# ANET3D_LCD2004_board.net
KiCad netlist of a schematic drawn in EAGLE
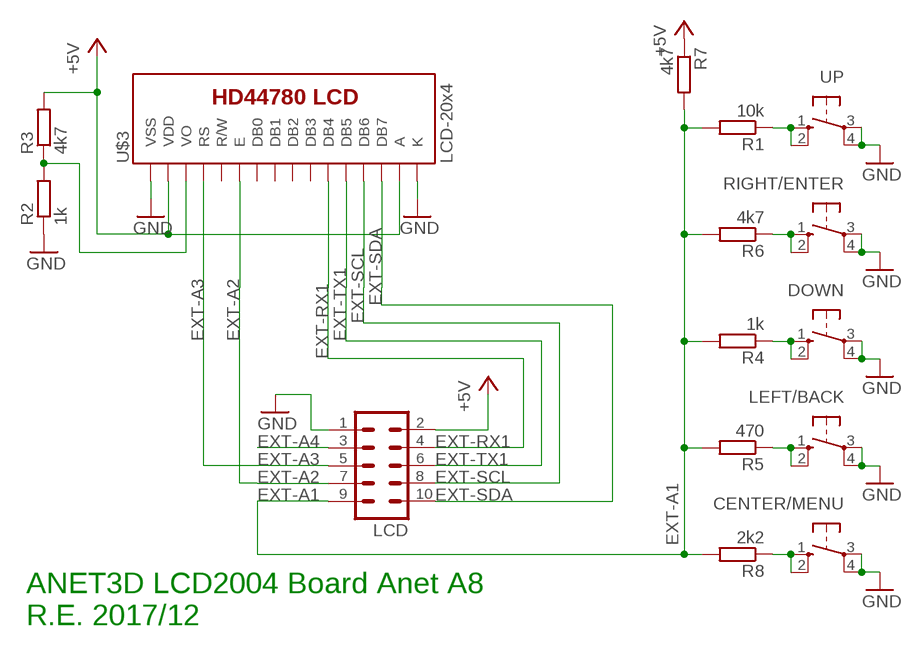
[diagram p0: schematic, sheet 1]

(export (version "E")
  (design (tool "Eeschema 10.0.6"))
  (components
    (comp (ref "CENTER/MENU")
      (value "40-XX")
      (footprint "eagle-import:B3F-40XX")
      (fields (field (name "MF") "OMRON COMPONENTS USA") (field (name "MPN") "B3F-4000"))
      (libsource (lib "eagle-import") (part "40-XX"))
    )
    (comp (ref "DOWN")
      (value "40-XX")
      (footprint "eagle-import:B3F-40XX")
      (fields (field (name "MF") "OMRON COMPONENTS USA") (field (name "MPN") "B3F-4000"))
      (libsource (lib "eagle-import") (part "40-XX"))
    )
    (comp (ref "LCD1")
      (value "LCD")
      (footprint "eagle-import:ML10")
      (libsource (lib "eagle-import") (part "ML10"))
    )
    (comp (ref "LEFT/BACK")
      (value "40-XX")
      (footprint "eagle-import:B3F-40XX")
      (fields (field (name "MF") "OMRON COMPONENTS USA") (field (name "MPN") "B3F-4000"))
      (libsource (lib "eagle-import") (part "40-XX"))
    )
    (comp (ref "R1")
      (value "10k")
      (footprint "eagle-import:R0805")
      (libsource (lib "eagle-import") (part "R-EU_R0805"))
    )
    (comp (ref "R2")
      (value "1k")
      (footprint "eagle-import:R0805")
      (libsource (lib "eagle-import") (part "R-EU_R0805"))
    )
    (comp (ref "R3")
      (value "4k7")
      (footprint "eagle-import:R0805")
      (libsource (lib "eagle-import") (part "R-EU_R0805"))
    )
    (comp (ref "R4")
      (value "1k")
      (footprint "eagle-import:R0805")
      (libsource (lib "eagle-import") (part "R-EU_R0805"))
    )
    (comp (ref "R5")
      (value "470")
      (footprint "eagle-import:R0805")
      (libsource (lib "eagle-import") (part "R-EU_R0805"))
    )
    (comp (ref "R6")
      (value "4k7")
      (footprint "eagle-import:R0805")
      (libsource (lib "eagle-import") (part "R-EU_R0805"))
    )
    (comp (ref "R7")
      (value "4k7")
      (footprint "eagle-import:R0805")
      (libsource (lib "eagle-import") (part "R-EU_R0805"))
    )
    (comp (ref "R8")
      (value "2k2")
      (footprint "eagle-import:R0805")
      (libsource (lib "eagle-import") (part "R-EU_R0805"))
    )
    (comp (ref "RIGHT/ENTER")
      (value "40-XX")
      (footprint "eagle-import:B3F-40XX")
      (fields (field (name "MF") "OMRON COMPONENTS USA") (field (name "MPN") "B3F-4000"))
      (libsource (lib "eagle-import") (part "40-XX"))
    )
    (comp (ref "U$3")
      (value "LCD-20x4")
      (footprint "eagle-import:LCD-20X4-4HOLES")
      (libsource (lib "eagle-import") (part "LCD-HD4478020X4-4HOLES4-HOLES"))
    )
    (comp (ref "UP")
      (value "40-XX")
      (footprint "eagle-import:B3F-40XX")
      (fields (field (name "MF") "OMRON COMPONENTS USA") (field (name "MPN") "B3F-4000"))
      (libsource (lib "eagle-import") (part "40-XX"))
    )
  )
  (nets
    (net (code "1") (name "+5V") (class "Default")
      (node (ref "LCD1") (pin "2") (pinfunction "2_2") (pintype "passive"))
      (node (ref "R3") (pin "2") (pinfunction "2_2") (pintype "passive"))
      (node (ref "R7") (pin "1") (pinfunction "1_1") (pintype "passive"))
      (node (ref "U$3") (pin "P$15") (pinfunction "A_P$15") (pintype "power_in"))
      (node (ref "U$3") (pin "P$2") (pinfunction "VDD_P$2") (pintype "power_in"))
    )
    (net (code "2") (name "/EXT-A1") (class "Default")
      (node (ref "LCD1") (pin "9") (pinfunction "9_9") (pintype "passive"))
      (node (ref "R1") (pin "2") (pinfunction "2_2") (pintype "passive"))
      (node (ref "R4") (pin "2") (pinfunction "2_2") (pintype "passive"))
      (node (ref "R5") (pin "2") (pinfunction "2_2") (pintype "passive"))
      (node (ref "R6") (pin "2") (pinfunction "2_2") (pintype "passive"))
      (node (ref "R7") (pin "2") (pinfunction "2_2") (pintype "passive"))
      (node (ref "R8") (pin "2") (pinfunction "2_2") (pintype "passive"))
    )
    (net (code "3") (name "/EXT-A2") (class "Default")
      (node (ref "LCD1") (pin "7") (pinfunction "7_7") (pintype "passive"))
      (node (ref "U$3") (pin "P$6") (pinfunction "E_P$6") (pintype "input"))
    )
    (net (code "4") (name "/EXT-A3") (class "Default")
      (node (ref "LCD1") (pin "5") (pinfunction "5_5") (pintype "passive"))
      (node (ref "U$3") (pin "P$4") (pinfunction "RS_P$4") (pintype "input"))
    )
    (net (code "5") (name "/EXT-A4") (class "Default")
      (node (ref "LCD1") (pin "3") (pinfunction "3_3") (pintype "passive"))
    )
    (net (code "6") (name "/EXT-RX1") (class "Default")
      (node (ref "LCD1") (pin "4") (pinfunction "4_4") (pintype "passive"))
      (node (ref "U$3") (pin "P$11") (pinfunction "DB4_P$11") (pintype "bidirectional"))
    )
    (net (code "7") (name "/EXT-SCL") (class "Default")
      (node (ref "LCD1") (pin "8") (pinfunction "8_8") (pintype "passive"))
      (node (ref "U$3") (pin "P$13") (pinfunction "DB6_P$13") (pintype "bidirectional"))
    )
    (net (code "8") (name "/EXT-SDA") (class "Default")
      (node (ref "LCD1") (pin "10") (pinfunction "10_10") (pintype "passive"))
      (node (ref "U$3") (pin "P$14") (pinfunction "DB7_P$14") (pintype "bidirectional"))
    )
    (net (code "9") (name "/EXT-TX1") (class "Default")
      (node (ref "LCD1") (pin "6") (pinfunction "6_6") (pintype "passive"))
      (node (ref "U$3") (pin "P$12") (pinfunction "DB5_P$12") (pintype "bidirectional"))
    )
    (net (code "10") (name "GND") (class "Default")
      (node (ref "CENTER/MENU") (pin "3") (pinfunction "P_3") (pintype "passive"))
      (node (ref "CENTER/MENU") (pin "4") (pinfunction "P1_4") (pintype "passive"))
      (node (ref "DOWN") (pin "3") (pinfunction "P_3") (pintype "passive"))
      (node (ref "DOWN") (pin "4") (pinfunction "P1_4") (pintype "passive"))
      (node (ref "LCD1") (pin "1") (pinfunction "1_1") (pintype "passive"))
      (node (ref "LEFT/BACK") (pin "3") (pinfunction "P_3") (pintype "passive"))
      (node (ref "LEFT/BACK") (pin "4") (pinfunction "P1_4") (pintype "passive"))
      (node (ref "R2") (pin "1") (pinfunction "1_1") (pintype "passive"))
      (node (ref "RIGHT/ENTER") (pin "3") (pinfunction "P_3") (pintype "passive"))
      (node (ref "RIGHT/ENTER") (pin "4") (pinfunction "P1_4") (pintype "passive"))
      (node (ref "U$3") (pin "P$1") (pinfunction "VSS_P$1") (pintype "power_in"))
      (node (ref "U$3") (pin "P$16") (pinfunction "K_P$16") (pintype "power_in"))
      (node (ref "UP") (pin "3") (pinfunction "P_3") (pintype "passive"))
      (node (ref "UP") (pin "4") (pinfunction "P1_4") (pintype "passive"))
    )
    (net (code "11") (name "Net-(CENTER/MENU-S)") (class "Default")
      (node (ref "CENTER/MENU") (pin "1") (pinfunction "S_1") (pintype "passive"))
      (node (ref "CENTER/MENU") (pin "2") (pinfunction "S1_2") (pintype "passive"))
      (node (ref "R8") (pin "1") (pinfunction "1_1") (pintype "passive"))
    )
    (net (code "12") (name "Net-(DOWN-S)") (class "Default")
      (node (ref "DOWN") (pin "1") (pinfunction "S_1") (pintype "passive"))
      (node (ref "DOWN") (pin "2") (pinfunction "S1_2") (pintype "passive"))
      (node (ref "R4") (pin "1") (pinfunction "1_1") (pintype "passive"))
    )
    (net (code "13") (name "Net-(LEFT/BACK-S)") (class "Default")
      (node (ref "LEFT/BACK") (pin "1") (pinfunction "S_1") (pintype "passive"))
      (node (ref "LEFT/BACK") (pin "2") (pinfunction "S1_2") (pintype "passive"))
      (node (ref "R5") (pin "1") (pinfunction "1_1") (pintype "passive"))
    )
    (net (code "14") (name "Net-(RIGHT/ENTER-S)") (class "Default")
      (node (ref "R6") (pin "1") (pinfunction "1_1") (pintype "passive"))
      (node (ref "RIGHT/ENTER") (pin "1") (pinfunction "S_1") (pintype "passive"))
      (node (ref "RIGHT/ENTER") (pin "2") (pinfunction "S1_2") (pintype "passive"))
    )
    (net (code "15") (name "Net-(U$3-VO)") (class "Default")
      (node (ref "R2") (pin "2") (pinfunction "2_2") (pintype "passive"))
      (node (ref "R3") (pin "1") (pinfunction "1_1") (pintype "passive"))
      (node (ref "U$3") (pin "P$3") (pinfunction "VO_P$3") (pintype "bidirectional"))
    )
    (net (code "16") (name "Net-(UP-S)") (class "Default")
      (node (ref "R1") (pin "1") (pinfunction "1_1") (pintype "passive"))
      (node (ref "UP") (pin "1") (pinfunction "S_1") (pintype "passive"))
      (node (ref "UP") (pin "2") (pinfunction "S1_2") (pintype "passive"))
    )
    (net (code "17") (name "unconnected-(U$3-DB0-PadP$7)") (class "Default")
      (node (ref "U$3") (pin "P$7") (pinfunction "DB0_P$7") (pintype "bidirectional"))
    )
    (net (code "18") (name "unconnected-(U$3-DB1-PadP$8)") (class "Default")
      (node (ref "U$3") (pin "P$8") (pinfunction "DB1_P$8") (pintype "bidirectional"))
    )
    (net (code "19") (name "unconnected-(U$3-DB2-PadP$9)") (class "Default")
      (node (ref "U$3") (pin "P$9") (pinfunction "DB2_P$9") (pintype "bidirectional"))
    )
    (net (code "20") (name "unconnected-(U$3-DB3-PadP$10)") (class "Default")
      (node (ref "U$3") (pin "P$10") (pinfunction "DB3_P$10") (pintype "bidirectional"))
    )
    (net (code "21") (name "unconnected-(U$3-R{slash}W-PadP$5)") (class "Default")
      (node (ref "U$3") (pin "P$5") (pinfunction "R/W_P$5") (pintype "input"))
    )
  )
)
